# STM32.net
KiCad netlist of a schematic drawn in Altium Designer
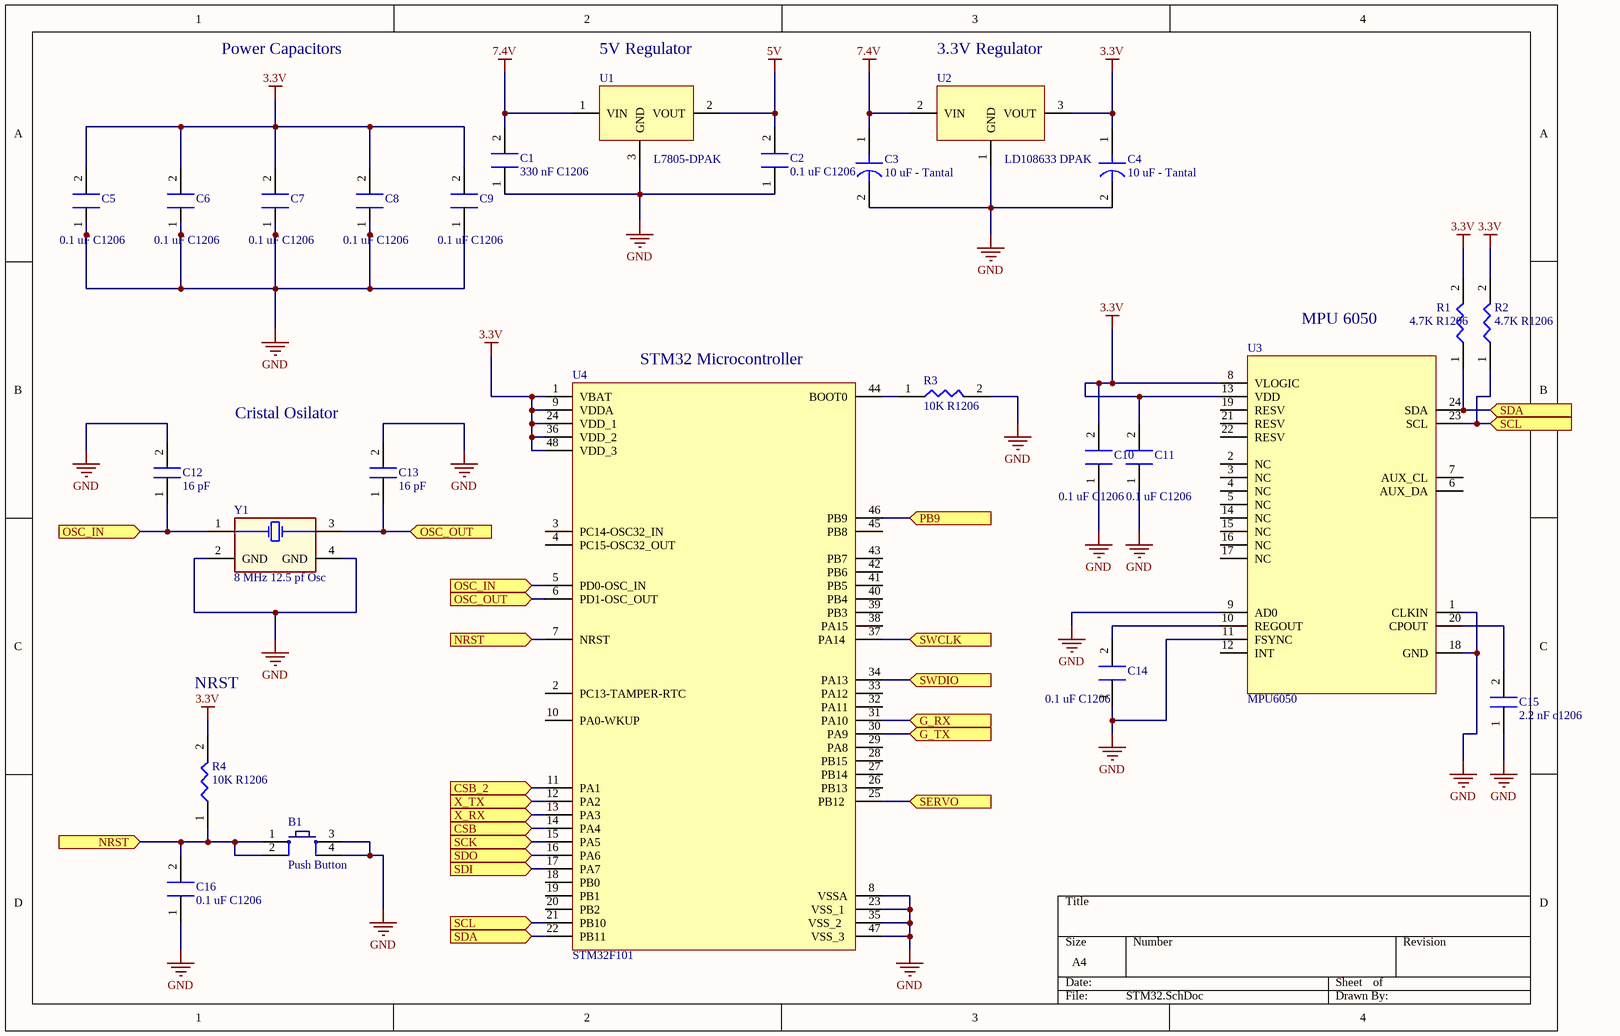
[diagram p0: STM32.SchDoc]

(export (version "E")
  (design (tool "Eeschema 10.0.6"))
  (components
    (comp (ref "B1")
      (value "Push Button")
      (footprint "PUSB BUTTON-SMD")
      (description "Smd Push Button")
      (libsource (lib "Stm32") (part "Push Button"))
    )
    (comp (ref "C1")
      (value "330 nF C1206")
      (footprint "C1206")
      (libsource (lib "Stm32") (part "330 nF C1206"))
    )
    (comp (ref "C2")
      (value "0.1 uF C1206")
      (footprint "C1206")
      (libsource (lib "Stm32") (part "0.1 uF C1206"))
    )
    (comp (ref "C3")
      (value "10 uF - Tantal")
      (footprint "C1206- TANTAL")
      (libsource (lib "Stm32") (part "10 uF - Tantal"))
    )
    (comp (ref "C4")
      (value "10 uF - Tantal")
      (footprint "C1206- TANTAL")
      (libsource (lib "Stm32") (part "10 uF - Tantal"))
    )
    (comp (ref "C5")
      (value "0.1 uF C1206")
      (footprint "C1206")
      (libsource (lib "Stm32") (part "0.1 uF C1206"))
    )
    (comp (ref "C6")
      (value "0.1 uF C1206")
      (footprint "C1206")
      (libsource (lib "Stm32") (part "0.1 uF C1206"))
    )
    (comp (ref "C7")
      (value "0.1 uF C1206")
      (footprint "C1206")
      (libsource (lib "Stm32") (part "0.1 uF C1206"))
    )
    (comp (ref "C8")
      (value "0.1 uF C1206")
      (footprint "C1206")
      (libsource (lib "Stm32") (part "0.1 uF C1206"))
    )
    (comp (ref "C9")
      (value "0.1 uF C1206")
      (footprint "C1206")
      (libsource (lib "Stm32") (part "0.1 uF C1206"))
    )
    (comp (ref "C10")
      (value "0.1 uF C1206")
      (footprint "C1206")
      (libsource (lib "Stm32") (part "0.1 uF C1206"))
    )
    (comp (ref "C11")
      (value "0.1 uF C1206")
      (footprint "C1206")
      (libsource (lib "Stm32") (part "0.1 uF C1206"))
    )
    (comp (ref "C12") (value "16 pF") (footprint "C1206") (libsource (lib "Stm32") (part "16 pF")))
    (comp (ref "C13") (value "16 pF") (footprint "C1206") (libsource (lib "Stm32") (part "16 pF")))
    (comp (ref "C14")
      (value "0.1 uF C1206")
      (footprint "C1206")
      (libsource (lib "Stm32") (part "0.1 uF C1206"))
    )
    (comp (ref "C15")
      (value "2.2 nF c1206")
      (footprint "C1206")
      (libsource (lib "Stm32") (part "2.2 nF c1206"))
    )
    (comp (ref "C16")
      (value "0.1 uF C1206")
      (footprint "C1206")
      (libsource (lib "Stm32") (part "0.1 uF C1206"))
    )
    (comp (ref "R1")
      (value "4.7K R1206")
      (footprint "R1206 Resıstor")
      (libsource (lib "Stm32") (part "4.7K R1206"))
    )
    (comp (ref "R2")
      (value "4.7K R1206")
      (footprint "R1206 Resıstor")
      (libsource (lib "Stm32") (part "4.7K R1206"))
    )
    (comp (ref "R3")
      (value "10K R1206")
      (footprint "R1206 Resıstor")
      (libsource (lib "Stm32") (part "10K R1206"))
    )
    (comp (ref "R4")
      (value "10K R1206")
      (footprint "R1206 Resıstor")
      (libsource (lib "Stm32") (part "10K R1206"))
    )
    (comp (ref "U1")
      (value "L7805-DPAK")
      (footprint "DPAK228P972X230-3N")
      (description "L7805 5V REGULATOR. SMD PAKET")
      (libsource (lib "Stm32") (part "L7805-DPAK"))
    )
    (comp (ref "U2")
      (value "LD108633 DPAK")
      (footprint "DPAK228P972X230-3N")
      (description "LD1086 3.3V REGULATOR")
      (libsource (lib "Stm32") (part "LD108633 DPAK"))
    )
    (comp (ref "U3")
      (value "MPU6050")
      (footprint "QFN50P400X400X90_HS-25N")
      (description "MPU6050 GYRO")
      (libsource (lib "Stm32") (part "MPU6050"))
    )
    (comp (ref "U4")
      (value "STM32F101")
      (footprint "LQFP48-STM")
      (description "STM32F101 48 PİNLİ MİKROİŞLEMCİ")
      (libsource (lib "Stm32") (part "STM32F101"))
    )
    (comp (ref "Y1")
      (value "8 MHz 12.5 pf Osc")
      (footprint "8 MHZ Osc.")
      (libsource (lib "Stm32") (part "8 MHz 12.5 pf Osc"))
    )
  )
  (nets
    (net (code "1") (name "/CSB") (class "Default")
      (node (ref "U4") (pin "14") (pinfunction "PA4_14") (pintype "passive"))
    )
    (net (code "2") (name "/CSB_2") (class "Default")
      (node (ref "U4") (pin "11") (pinfunction "PA1_11") (pintype "passive"))
    )
    (net (code "3") (name "/G_RX") (class "Default")
      (node (ref "U4") (pin "31") (pinfunction "PA10_31") (pintype "passive"))
    )
    (net (code "4") (name "/G_TX") (class "Default")
      (node (ref "U4") (pin "30") (pinfunction "PA9_30") (pintype "passive"))
    )
    (net (code "5") (name "/NRST") (class "Default")
      (node (ref "B1") (pin "1") (pinfunction "1_1") (pintype "passive"))
      (node (ref "B1") (pin "2") (pinfunction "2_2") (pintype "passive"))
      (node (ref "C16") (pin "2") (pinfunction "2_2") (pintype "passive"))
      (node (ref "R4") (pin "1") (pinfunction "1_1") (pintype "passive"))
      (node (ref "U4") (pin "7") (pinfunction "NRST_7") (pintype "passive"))
    )
    (net (code "6") (name "/OSC_IN") (class "Default")
      (node (ref "C12") (pin "1") (pinfunction "1_1") (pintype "passive"))
      (node (ref "U4") (pin "5") (pinfunction "PD0-OSC_IN_5") (pintype "passive"))
      (node (ref "Y1") (pin "1") (pintype "power_in"))
    )
    (net (code "7") (name "/OSC_OUT") (class "Default")
      (node (ref "C13") (pin "1") (pinfunction "1_1") (pintype "passive"))
      (node (ref "U4") (pin "6") (pinfunction "PD1-OSC_OUT_6") (pintype "passive"))
      (node (ref "Y1") (pin "3") (pintype "passive"))
    )
    (net (code "8") (name "/PB9") (class "Default")
      (node (ref "U4") (pin "46") (pinfunction "PB9_46") (pintype "passive"))
    )
    (net (code "9") (name "/SCK") (class "Default")
      (node (ref "U4") (pin "15") (pinfunction "PA5_15") (pintype "passive"))
    )
    (net (code "10") (name "/SCL") (class "Default")
      (node (ref "R2") (pin "1") (pinfunction "1_1") (pintype "passive"))
      (node (ref "U3") (pin "23") (pinfunction "SCL_23") (pintype "passive"))
      (node (ref "U4") (pin "21") (pinfunction "PB10_21") (pintype "passive"))
    )
    (net (code "11") (name "/SDA") (class "Default")
      (node (ref "R1") (pin "1") (pinfunction "1_1") (pintype "passive"))
      (node (ref "U3") (pin "24") (pinfunction "SDA_24") (pintype "passive"))
      (node (ref "U4") (pin "22") (pinfunction "PB11_22") (pintype "passive"))
    )
    (net (code "12") (name "/SDI") (class "Default")
      (node (ref "U4") (pin "17") (pinfunction "PA7_17") (pintype "passive"))
    )
    (net (code "13") (name "/SDO") (class "Default")
      (node (ref "U4") (pin "16") (pinfunction "PA6_16") (pintype "passive"))
    )
    (net (code "14") (name "/SERVO") (class "Default")
      (node (ref "U4") (pin "25") (pinfunction "PB12_25") (pintype "passive"))
    )
    (net (code "15") (name "/SWCLK") (class "Default")
      (node (ref "U4") (pin "37") (pinfunction "PA14_37") (pintype "passive"))
    )
    (net (code "16") (name "/SWDIO") (class "Default")
      (node (ref "U4") (pin "34") (pinfunction "PA13_34") (pintype "passive"))
    )
    (net (code "17") (name "/X_RX") (class "Default")
      (node (ref "U4") (pin "13") (pinfunction "PA3_13") (pintype "passive"))
    )
    (net (code "18") (name "/X_TX") (class "Default")
      (node (ref "U4") (pin "12") (pinfunction "PA2_12") (pintype "passive"))
    )
    (net (code "19") (name "3.3V") (class "Default")
      (node (ref "C10") (pin "2") (pinfunction "2_2") (pintype "passive"))
      (node (ref "C11") (pin "2") (pinfunction "2_2") (pintype "passive"))
      (node (ref "C4") (pin "1") (pinfunction "1_1") (pintype "passive"))
      (node (ref "C5") (pin "2") (pinfunction "2_2") (pintype "passive"))
      (node (ref "C6") (pin "2") (pinfunction "2_2") (pintype "passive"))
      (node (ref "C7") (pin "2") (pinfunction "2_2") (pintype "passive"))
      (node (ref "C8") (pin "2") (pinfunction "2_2") (pintype "passive"))
      (node (ref "C9") (pin "2") (pinfunction "2_2") (pintype "passive"))
      (node (ref "R1") (pin "2") (pinfunction "2_2") (pintype "passive"))
      (node (ref "R2") (pin "2") (pinfunction "2_2") (pintype "passive"))
      (node (ref "R4") (pin "2") (pinfunction "2_2") (pintype "passive"))
      (node (ref "U2") (pin "3") (pinfunction "VOUT_3") (pintype "passive"))
      (node (ref "U3") (pin "13") (pinfunction "VDD_13") (pintype "passive"))
      (node (ref "U3") (pin "8") (pinfunction "VLOGIC_8") (pintype "passive"))
      (node (ref "U4") (pin "1") (pinfunction "VBAT_1") (pintype "passive"))
      (node (ref "U4") (pin "24") (pinfunction "VDD_1_24") (pintype "passive"))
      (node (ref "U4") (pin "36") (pinfunction "VDD_2_36") (pintype "passive"))
      (node (ref "U4") (pin "48") (pinfunction "VDD_3_48") (pintype "passive"))
      (node (ref "U4") (pin "9") (pinfunction "VDDA_9") (pintype "passive"))
    )
    (net (code "20") (name "5V") (class "Default")
      (node (ref "C2") (pin "2") (pinfunction "2_2") (pintype "passive"))
      (node (ref "U1") (pin "2") (pinfunction "VOUT_2") (pintype "passive"))
    )
    (net (code "21") (name "7.4V") (class "Default")
      (node (ref "C1") (pin "2") (pinfunction "2_2") (pintype "passive"))
      (node (ref "C3") (pin "1") (pinfunction "1_1") (pintype "passive"))
      (node (ref "U1") (pin "1") (pinfunction "VIN_1") (pintype "passive"))
      (node (ref "U2") (pin "2") (pinfunction "VIN_2") (pintype "passive"))
    )
    (net (code "22") (name "GND") (class "Default")
      (node (ref "B1") (pin "3") (pinfunction "3_3") (pintype "passive"))
      (node (ref "B1") (pin "4") (pinfunction "4_4") (pintype "passive"))
      (node (ref "C1") (pin "1") (pinfunction "1_1") (pintype "passive"))
      (node (ref "C10") (pin "1") (pinfunction "1_1") (pintype "passive"))
      (node (ref "C11") (pin "1") (pinfunction "1_1") (pintype "passive"))
      (node (ref "C12") (pin "2") (pinfunction "2_2") (pintype "passive"))
      (node (ref "C13") (pin "2") (pinfunction "2_2") (pintype "passive"))
      (node (ref "C14") (pin "1") (pinfunction "1_1") (pintype "passive"))
      (node (ref "C15") (pin "1") (pinfunction "1_1") (pintype "passive"))
      (node (ref "C16") (pin "1") (pinfunction "1_1") (pintype "passive"))
      (node (ref "C2") (pin "1") (pinfunction "1_1") (pintype "passive"))
      (node (ref "C3") (pin "2") (pinfunction "2_2") (pintype "passive"))
      (node (ref "C4") (pin "2") (pinfunction "2_2") (pintype "passive"))
      (node (ref "C5") (pin "1") (pinfunction "1_1") (pintype "passive"))
      (node (ref "C6") (pin "1") (pinfunction "1_1") (pintype "passive"))
      (node (ref "C7") (pin "1") (pinfunction "1_1") (pintype "passive"))
      (node (ref "C8") (pin "1") (pinfunction "1_1") (pintype "passive"))
      (node (ref "C9") (pin "1") (pinfunction "1_1") (pintype "passive"))
      (node (ref "R3") (pin "2") (pinfunction "2_2") (pintype "passive"))
      (node (ref "U1") (pin "3") (pinfunction "GND_3") (pintype "passive"))
      (node (ref "U2") (pin "1") (pinfunction "GND_1") (pintype "passive"))
      (node (ref "U3") (pin "1") (pinfunction "CLKIN_1") (pintype "passive"))
      (node (ref "U3") (pin "11") (pinfunction "FSYNC_11") (pintype "passive"))
      (node (ref "U3") (pin "18") (pinfunction "GND_18") (pintype "passive"))
      (node (ref "U3") (pin "9") (pinfunction "AD0_9") (pintype "passive"))
      (node (ref "U4") (pin "23") (pinfunction "VSS_1_23") (pintype "passive"))
      (node (ref "U4") (pin "35") (pinfunction "VSS_2_35") (pintype "passive"))
      (node (ref "U4") (pin "47") (pinfunction "VSS_3_47") (pintype "passive"))
      (node (ref "U4") (pin "8") (pinfunction "VSSA_8") (pintype "passive"))
      (node (ref "Y1") (pin "2") (pinfunction "GND_2") (pintype "power_in"))
      (node (ref "Y1") (pin "4") (pinfunction "GND_4") (pintype "passive"))
    )
    (net (code "23") (name "Net-(U3-CPOUT)") (class "Default")
      (node (ref "C15") (pin "2") (pinfunction "2_2") (pintype "passive"))
      (node (ref "U3") (pin "20") (pinfunction "CPOUT_20") (pintype "passive"))
    )
    (net (code "24") (name "Net-(U3-REGOUT)") (class "Default")
      (node (ref "C14") (pin "2") (pinfunction "2_2") (pintype "passive"))
      (node (ref "U3") (pin "10") (pinfunction "REGOUT_10") (pintype "passive"))
    )
    (net (code "25") (name "Net-(U4-BOOT0)") (class "Default")
      (node (ref "R3") (pin "1") (pinfunction "1_1") (pintype "passive"))
      (node (ref "U4") (pin "44") (pinfunction "BOOT0_44") (pintype "passive"))
    )
    (net (code "26") (name "unconnected-(U3-AUX_CL-Pad7)") (class "Default")
      (node (ref "U3") (pin "7") (pinfunction "AUX_CL_7") (pintype "passive"))
    )
    (net (code "27") (name "unconnected-(U3-AUX_DA-Pad6)") (class "Default")
      (node (ref "U3") (pin "6") (pinfunction "AUX_DA_6") (pintype "passive"))
    )
    (net (code "28") (name "unconnected-(U3-INT-Pad12)") (class "Default")
      (node (ref "U3") (pin "12") (pinfunction "INT_12") (pintype "passive"))
    )
    (net (code "29") (name "unconnected-(U3-NC-Pad2)") (class "Default")
      (node (ref "U3") (pin "2") (pinfunction "NC_2") (pintype "passive"))
    )
    (net (code "30") (name "unconnected-(U3-NC-Pad3)") (class "Default")
      (node (ref "U3") (pin "3") (pinfunction "NC_3") (pintype "passive"))
    )
    (net (code "31") (name "unconnected-(U3-NC-Pad4)") (class "Default")
      (node (ref "U3") (pin "4") (pinfunction "NC_4") (pintype "passive"))
    )
    (net (code "32") (name "unconnected-(U3-NC-Pad5)") (class "Default")
      (node (ref "U3") (pin "5") (pinfunction "NC_5") (pintype "passive"))
    )
    (net (code "33") (name "unconnected-(U3-NC-Pad14)") (class "Default")
      (node (ref "U3") (pin "14") (pinfunction "NC_14") (pintype "passive"))
    )
    (net (code "34") (name "unconnected-(U3-NC-Pad15)") (class "Default")
      (node (ref "U3") (pin "15") (pinfunction "NC_15") (pintype "passive"))
    )
    (net (code "35") (name "unconnected-(U3-NC-Pad16)") (class "Default")
      (node (ref "U3") (pin "16") (pinfunction "NC_16") (pintype "passive"))
    )
    (net (code "36") (name "unconnected-(U3-NC-Pad17)") (class "Default")
      (node (ref "U3") (pin "17") (pinfunction "NC_17") (pintype "passive"))
    )
    (net (code "37") (name "unconnected-(U3-RESV-Pad19)") (class "Default")
      (node (ref "U3") (pin "19") (pinfunction "RESV_19") (pintype "passive"))
    )
    (net (code "38") (name "unconnected-(U3-RESV-Pad21)") (class "Default")
      (node (ref "U3") (pin "21") (pinfunction "RESV_21") (pintype "passive"))
    )
    (net (code "39") (name "unconnected-(U3-RESV-Pad22)") (class "Default")
      (node (ref "U3") (pin "22") (pinfunction "RESV_22") (pintype "passive"))
    )
    (net (code "40") (name "unconnected-(U4-PA0-WKUP-Pad10)") (class "Default")
      (node (ref "U4") (pin "10") (pinfunction "PA0-WKUP_10") (pintype "passive"))
    )
    (net (code "41") (name "unconnected-(U4-PA8-Pad29)") (class "Default")
      (node (ref "U4") (pin "29") (pinfunction "PA8_29") (pintype "passive"))
    )
    (net (code "42") (name "unconnected-(U4-PA11-Pad32)") (class "Default")
      (node (ref "U4") (pin "32") (pinfunction "PA11_32") (pintype "passive"))
    )
    (net (code "43") (name "unconnected-(U4-PA12-Pad33)") (class "Default")
      (node (ref "U4") (pin "33") (pinfunction "PA12_33") (pintype "passive"))
    )
    (net (code "44") (name "unconnected-(U4-PA15-Pad38)") (class "Default")
      (node (ref "U4") (pin "38") (pinfunction "PA15_38") (pintype "passive"))
    )
    (net (code "45") (name "unconnected-(U4-PB0-Pad18)") (class "Default")
      (node (ref "U4") (pin "18") (pinfunction "PB0_18") (pintype "passive"))
    )
    (net (code "46") (name "unconnected-(U4-PB1-Pad19)") (class "Default")
      (node (ref "U4") (pin "19") (pinfunction "PB1_19") (pintype "passive"))
    )
    (net (code "47") (name "unconnected-(U4-PB2-Pad20)") (class "Default")
      (node (ref "U4") (pin "20") (pinfunction "PB2_20") (pintype "passive"))
    )
    (net (code "48") (name "unconnected-(U4-PB3-Pad39)") (class "Default")
      (node (ref "U4") (pin "39") (pinfunction "PB3_39") (pintype "passive"))
    )
    (net (code "49") (name "unconnected-(U4-PB4-Pad40)") (class "Default")
      (node (ref "U4") (pin "40") (pinfunction "PB4_40") (pintype "passive"))
    )
    (net (code "50") (name "unconnected-(U4-PB5-Pad41)") (class "Default")
      (node (ref "U4") (pin "41") (pinfunction "PB5_41") (pintype "passive"))
    )
    (net (code "51") (name "unconnected-(U4-PB6-Pad42)") (class "Default")
      (node (ref "U4") (pin "42") (pinfunction "PB6_42") (pintype "passive"))
    )
    (net (code "52") (name "unconnected-(U4-PB7-Pad43)") (class "Default")
      (node (ref "U4") (pin "43") (pinfunction "PB7_43") (pintype "passive"))
    )
    (net (code "53") (name "unconnected-(U4-PB8-Pad45)") (class "Default")
      (node (ref "U4") (pin "45") (pinfunction "PB8_45") (pintype "passive"))
    )
    (net (code "54") (name "unconnected-(U4-PB13-Pad26)") (class "Default")
      (node (ref "U4") (pin "26") (pinfunction "PB13_26") (pintype "passive"))
    )
    (net (code "55") (name "unconnected-(U4-PB14-Pad27)") (class "Default")
      (node (ref "U4") (pin "27") (pinfunction "PB14_27") (pintype "passive"))
    )
    (net (code "56") (name "unconnected-(U4-PB15-Pad28)") (class "Default")
      (node (ref "U4") (pin "28") (pinfunction "PB15_28") (pintype "passive"))
    )
    (net (code "57") (name "unconnected-(U4-PC13-TAMPER-RTC-Pad2)") (class "Default")
      (node (ref "U4") (pin "2") (pinfunction "PC13-TAMPER-RTC_2") (pintype "passive"))
    )
    (net (code "58") (name "unconnected-(U4-PC14-OSC32_IN-Pad3)") (class "Default")
      (node (ref "U4") (pin "3") (pinfunction "PC14-OSC32_IN_3") (pintype "passive"))
    )
    (net (code "59") (name "unconnected-(U4-PC15-OSC32_OUT-Pad4)") (class "Default")
      (node (ref "U4") (pin "4") (pinfunction "PC15-OSC32_OUT_4") (pintype "passive"))
    )
  )
)
